# CM5.net
KiCad netlist of a schematic drawn in Altium Designer
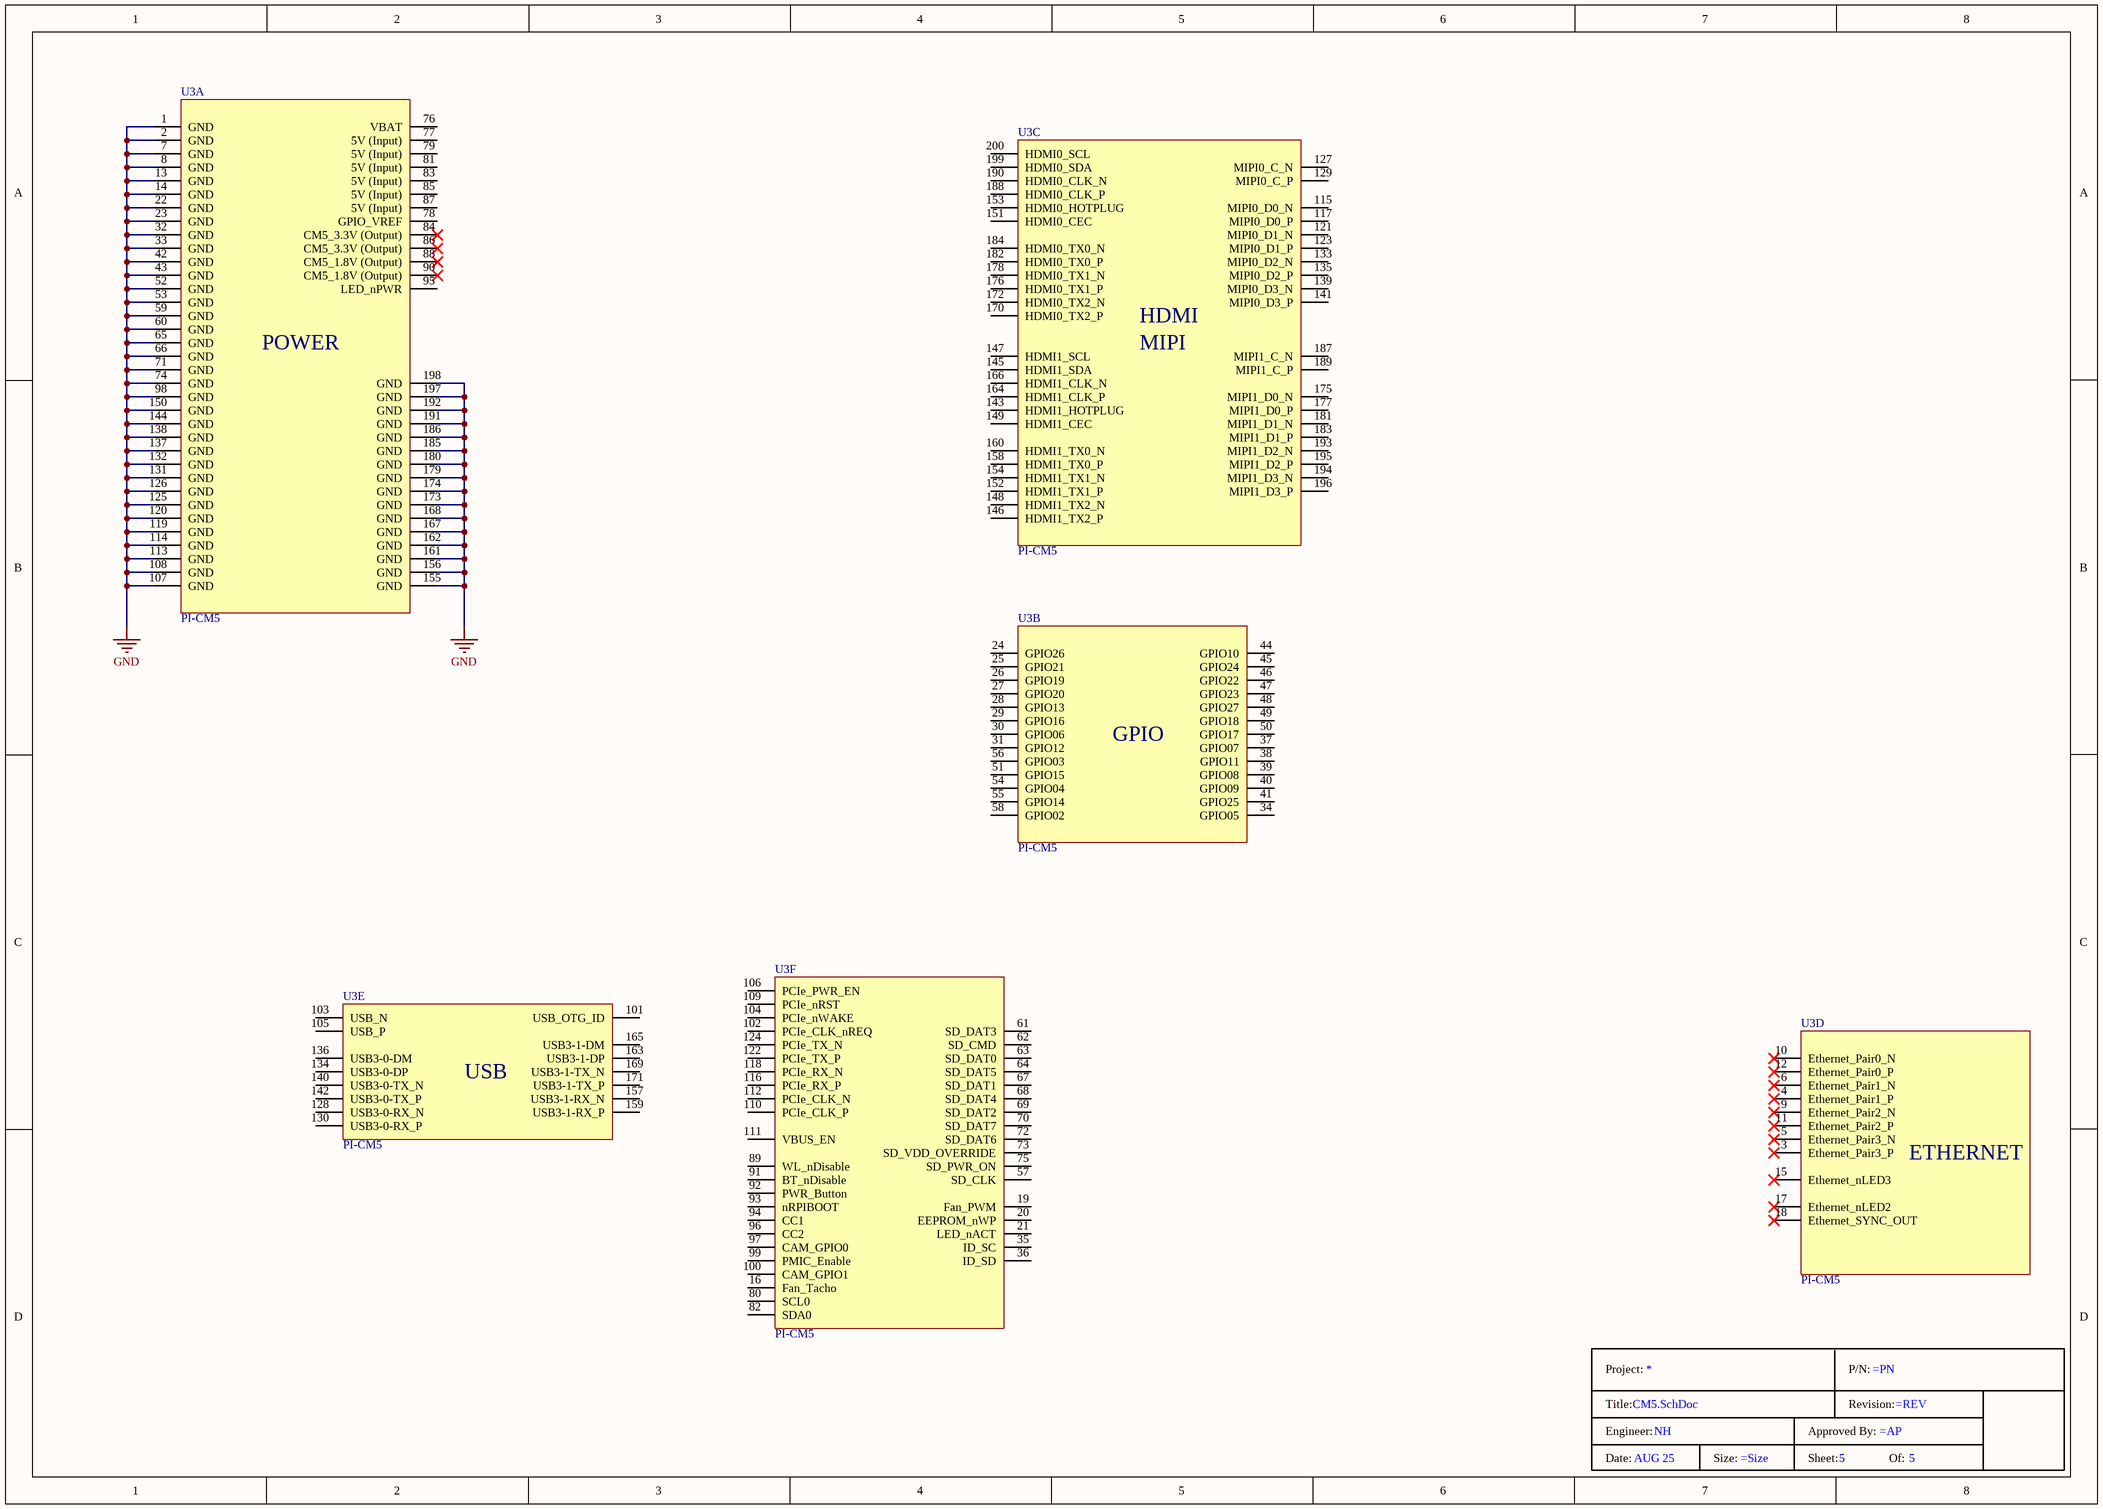
[diagram p0: CM5.SchDoc]

(export (version "E")
  (design (tool "Eeschema 10.0.6"))
  (components
    (comp (ref "*") (value "Tital_block_1") (libsource (lib "Graphical") (part "Tital_block_1")))
    (comp (ref "U3") (value "PI-CM5") (footprint "SC1562(PI-CM5)") (libsource (lib "IC") (part "PI-CM5")))
  )
  (nets
    (net (code "1") (name "GND") (class "Default")
      (node (ref "U3") (pin "1") (pinfunction "GND_1") (pintype "passive"))
      (node (ref "U3") (pin "107") (pinfunction "GND_107") (pintype "passive"))
      (node (ref "U3") (pin "108") (pinfunction "GND_108") (pintype "passive"))
      (node (ref "U3") (pin "113") (pinfunction "GND_113") (pintype "passive"))
      (node (ref "U3") (pin "114") (pinfunction "GND_114") (pintype "passive"))
      (node (ref "U3") (pin "119") (pinfunction "GND_119") (pintype "passive"))
      (node (ref "U3") (pin "120") (pinfunction "GND_120") (pintype "passive"))
      (node (ref "U3") (pin "125") (pinfunction "GND_125") (pintype "passive"))
      (node (ref "U3") (pin "126") (pinfunction "GND_126") (pintype "passive"))
      (node (ref "U3") (pin "13") (pinfunction "GND_13") (pintype "passive"))
      (node (ref "U3") (pin "131") (pinfunction "GND_131") (pintype "passive"))
      (node (ref "U3") (pin "132") (pinfunction "GND_132") (pintype "passive"))
      (node (ref "U3") (pin "137") (pinfunction "GND_137") (pintype "passive"))
      (node (ref "U3") (pin "138") (pinfunction "GND_138") (pintype "passive"))
      (node (ref "U3") (pin "14") (pinfunction "GND_14") (pintype "passive"))
      (node (ref "U3") (pin "144") (pinfunction "GND_144") (pintype "passive"))
      (node (ref "U3") (pin "150") (pinfunction "GND_150") (pintype "passive"))
      (node (ref "U3") (pin "155") (pinfunction "GND_155") (pintype "passive"))
      (node (ref "U3") (pin "156") (pinfunction "GND_156") (pintype "passive"))
      (node (ref "U3") (pin "161") (pinfunction "GND_161") (pintype "passive"))
      (node (ref "U3") (pin "162") (pinfunction "GND_162") (pintype "passive"))
      (node (ref "U3") (pin "167") (pinfunction "GND_167") (pintype "passive"))
      (node (ref "U3") (pin "168") (pinfunction "GND_168") (pintype "passive"))
      (node (ref "U3") (pin "173") (pinfunction "GND_173") (pintype "passive"))
      (node (ref "U3") (pin "174") (pinfunction "GND_174") (pintype "passive"))
      (node (ref "U3") (pin "179") (pinfunction "GND_179") (pintype "passive"))
      (node (ref "U3") (pin "180") (pinfunction "GND_180") (pintype "passive"))
      (node (ref "U3") (pin "185") (pinfunction "GND_185") (pintype "passive"))
      (node (ref "U3") (pin "186") (pinfunction "GND_186") (pintype "passive"))
      (node (ref "U3") (pin "191") (pinfunction "GND_191") (pintype "passive"))
      (node (ref "U3") (pin "192") (pinfunction "GND_192") (pintype "passive"))
      (node (ref "U3") (pin "197") (pinfunction "GND_197") (pintype "passive"))
      (node (ref "U3") (pin "198") (pinfunction "GND_198") (pintype "passive"))
      (node (ref "U3") (pin "2") (pinfunction "GND_2") (pintype "passive"))
      (node (ref "U3") (pin "22") (pinfunction "GND_22") (pintype "passive"))
      (node (ref "U3") (pin "23") (pinfunction "GND_23") (pintype "passive"))
      (node (ref "U3") (pin "32") (pinfunction "GND_32") (pintype "passive"))
      (node (ref "U3") (pin "33") (pinfunction "GND_33") (pintype "passive"))
      (node (ref "U3") (pin "42") (pinfunction "GND_42") (pintype "passive"))
      (node (ref "U3") (pin "43") (pinfunction "GND_43") (pintype "passive"))
      (node (ref "U3") (pin "52") (pinfunction "GND_52") (pintype "passive"))
      (node (ref "U3") (pin "53") (pinfunction "GND_53") (pintype "passive"))
      (node (ref "U3") (pin "59") (pinfunction "GND_59") (pintype "passive"))
      (node (ref "U3") (pin "60") (pinfunction "GND_60") (pintype "passive"))
      (node (ref "U3") (pin "65") (pinfunction "GND_65") (pintype "passive"))
      (node (ref "U3") (pin "66") (pinfunction "GND_66") (pintype "passive"))
      (node (ref "U3") (pin "7") (pinfunction "GND_7") (pintype "passive"))
      (node (ref "U3") (pin "71") (pinfunction "GND_71") (pintype "passive"))
      (node (ref "U3") (pin "74") (pinfunction "GND_74") (pintype "passive"))
      (node (ref "U3") (pin "8") (pinfunction "GND_8") (pintype "passive"))
      (node (ref "U3") (pin "98") (pinfunction "GND_98") (pintype "passive"))
    )
    (net (code "2") (name "unconnected-(U3A-5V_(Input)-Pad77)") (class "Default")
      (node (ref "U3") (pin "77") (pinfunction "5V_(Input)_77") (pintype "passive"))
    )
    (net (code "3") (name "unconnected-(U3A-5V_(Input)-Pad79)") (class "Default")
      (node (ref "U3") (pin "79") (pinfunction "5V_(Input)_79") (pintype "passive"))
    )
    (net (code "4") (name "unconnected-(U3A-5V_(Input)-Pad81)") (class "Default")
      (node (ref "U3") (pin "81") (pinfunction "5V_(Input)_81") (pintype "passive"))
    )
    (net (code "5") (name "unconnected-(U3A-5V_(Input)-Pad83)") (class "Default")
      (node (ref "U3") (pin "83") (pinfunction "5V_(Input)_83") (pintype "passive"))
    )
    (net (code "6") (name "unconnected-(U3A-5V_(Input)-Pad85)") (class "Default")
      (node (ref "U3") (pin "85") (pinfunction "5V_(Input)_85") (pintype "passive"))
    )
    (net (code "7") (name "unconnected-(U3A-5V_(Input)-Pad87)") (class "Default")
      (node (ref "U3") (pin "87") (pinfunction "5V_(Input)_87") (pintype "passive"))
    )
    (net (code "8") (name "unconnected-(U3A-CM5_1.8V_(Output)-Pad88)") (class "Default")
      (node (ref "U3") (pin "88") (pinfunction "CM5_1.8V_(Output)_88") (pintype "passive+no_connect"))
    )
    (net (code "9") (name "unconnected-(U3A-CM5_1.8V_(Output)-Pad90)") (class "Default")
      (node (ref "U3") (pin "90") (pinfunction "CM5_1.8V_(Output)_90") (pintype "passive+no_connect"))
    )
    (net (code "10") (name "unconnected-(U3A-CM5_3.3V_(Output)-Pad84)") (class "Default")
      (node (ref "U3") (pin "84") (pinfunction "CM5_3.3V_(Output)_84") (pintype "passive+no_connect"))
    )
    (net (code "11") (name "unconnected-(U3A-CM5_3.3V_(Output)-Pad86)") (class "Default")
      (node (ref "U3") (pin "86") (pinfunction "CM5_3.3V_(Output)_86") (pintype "passive+no_connect"))
    )
    (net (code "12") (name "unconnected-(U3A-GPIO_VREF-Pad78)") (class "Default")
      (node (ref "U3") (pin "78") (pinfunction "GPIO_VREF_78") (pintype "passive"))
    )
    (net (code "13") (name "unconnected-(U3A-LED_nPWR-Pad95)") (class "Default")
      (node (ref "U3") (pin "95") (pinfunction "LED_nPWR_95") (pintype "passive"))
    )
    (net (code "14") (name "unconnected-(U3A-VBAT-Pad76)") (class "Default")
      (node (ref "U3") (pin "76") (pinfunction "VBAT_76") (pintype "passive"))
    )
    (net (code "15") (name "unconnected-(U3B-GPIO02-Pad58)") (class "Default")
      (node (ref "U3") (pin "58") (pinfunction "GPIO02_58") (pintype "passive"))
    )
    (net (code "16") (name "unconnected-(U3B-GPIO03-Pad56)") (class "Default")
      (node (ref "U3") (pin "56") (pinfunction "GPIO03_56") (pintype "passive"))
    )
    (net (code "17") (name "unconnected-(U3B-GPIO04-Pad54)") (class "Default")
      (node (ref "U3") (pin "54") (pinfunction "GPIO04_54") (pintype "passive"))
    )
    (net (code "18") (name "unconnected-(U3B-GPIO05-Pad34)") (class "Default")
      (node (ref "U3") (pin "34") (pinfunction "GPIO05_34") (pintype "passive"))
    )
    (net (code "19") (name "unconnected-(U3B-GPIO06-Pad30)") (class "Default")
      (node (ref "U3") (pin "30") (pinfunction "GPIO06_30") (pintype "passive"))
    )
    (net (code "20") (name "unconnected-(U3B-GPIO07-Pad37)") (class "Default")
      (node (ref "U3") (pin "37") (pinfunction "GPIO07_37") (pintype "passive"))
    )
    (net (code "21") (name "unconnected-(U3B-GPIO08-Pad39)") (class "Default")
      (node (ref "U3") (pin "39") (pinfunction "GPIO08_39") (pintype "passive"))
    )
    (net (code "22") (name "unconnected-(U3B-GPIO09-Pad40)") (class "Default")
      (node (ref "U3") (pin "40") (pinfunction "GPIO09_40") (pintype "passive"))
    )
    (net (code "23") (name "unconnected-(U3B-GPIO10-Pad44)") (class "Default")
      (node (ref "U3") (pin "44") (pinfunction "GPIO10_44") (pintype "passive"))
    )
    (net (code "24") (name "unconnected-(U3B-GPIO11-Pad38)") (class "Default")
      (node (ref "U3") (pin "38") (pinfunction "GPIO11_38") (pintype "passive"))
    )
    (net (code "25") (name "unconnected-(U3B-GPIO12-Pad31)") (class "Default")
      (node (ref "U3") (pin "31") (pinfunction "GPIO12_31") (pintype "passive"))
    )
    (net (code "26") (name "unconnected-(U3B-GPIO13-Pad28)") (class "Default")
      (node (ref "U3") (pin "28") (pinfunction "GPIO13_28") (pintype "passive"))
    )
    (net (code "27") (name "unconnected-(U3B-GPIO14-Pad55)") (class "Default")
      (node (ref "U3") (pin "55") (pinfunction "GPIO14_55") (pintype "passive"))
    )
    (net (code "28") (name "unconnected-(U3B-GPIO15-Pad51)") (class "Default")
      (node (ref "U3") (pin "51") (pinfunction "GPIO15_51") (pintype "passive"))
    )
    (net (code "29") (name "unconnected-(U3B-GPIO16-Pad29)") (class "Default")
      (node (ref "U3") (pin "29") (pinfunction "GPIO16_29") (pintype "passive"))
    )
    (net (code "30") (name "unconnected-(U3B-GPIO17-Pad50)") (class "Default")
      (node (ref "U3") (pin "50") (pinfunction "GPIO17_50") (pintype "passive"))
    )
    (net (code "31") (name "unconnected-(U3B-GPIO18-Pad49)") (class "Default")
      (node (ref "U3") (pin "49") (pinfunction "GPIO18_49") (pintype "passive"))
    )
    (net (code "32") (name "unconnected-(U3B-GPIO19-Pad26)") (class "Default")
      (node (ref "U3") (pin "26") (pinfunction "GPIO19_26") (pintype "passive"))
    )
    (net (code "33") (name "unconnected-(U3B-GPIO20-Pad27)") (class "Default")
      (node (ref "U3") (pin "27") (pinfunction "GPIO20_27") (pintype "passive"))
    )
    (net (code "34") (name "unconnected-(U3B-GPIO21-Pad25)") (class "Default")
      (node (ref "U3") (pin "25") (pinfunction "GPIO21_25") (pintype "passive"))
    )
    (net (code "35") (name "unconnected-(U3B-GPIO22-Pad46)") (class "Default")
      (node (ref "U3") (pin "46") (pinfunction "GPIO22_46") (pintype "passive"))
    )
    (net (code "36") (name "unconnected-(U3B-GPIO23-Pad47)") (class "Default")
      (node (ref "U3") (pin "47") (pinfunction "GPIO23_47") (pintype "passive"))
    )
    (net (code "37") (name "unconnected-(U3B-GPIO24-Pad45)") (class "Default")
      (node (ref "U3") (pin "45") (pinfunction "GPIO24_45") (pintype "passive"))
    )
    (net (code "38") (name "unconnected-(U3B-GPIO25-Pad41)") (class "Default")
      (node (ref "U3") (pin "41") (pinfunction "GPIO25_41") (pintype "passive"))
    )
    (net (code "39") (name "unconnected-(U3B-GPIO26-Pad24)") (class "Default")
      (node (ref "U3") (pin "24") (pinfunction "GPIO26_24") (pintype "passive"))
    )
    (net (code "40") (name "unconnected-(U3B-GPIO27-Pad48)") (class "Default")
      (node (ref "U3") (pin "48") (pinfunction "GPIO27_48") (pintype "passive"))
    )
    (net (code "41") (name "unconnected-(U3C-HDMI0_CEC-Pad151)") (class "Default")
      (node (ref "U3") (pin "151") (pinfunction "HDMI0_CEC_151") (pintype "passive"))
    )
    (net (code "42") (name "unconnected-(U3C-HDMI0_CLK_N-Pad190)") (class "Default")
      (node (ref "U3") (pin "190") (pinfunction "HDMI0_CLK_N_190") (pintype "passive"))
    )
    (net (code "43") (name "unconnected-(U3C-HDMI0_CLK_P-Pad188)") (class "Default")
      (node (ref "U3") (pin "188") (pinfunction "HDMI0_CLK_P_188") (pintype "passive"))
    )
    (net (code "44") (name "unconnected-(U3C-HDMI0_HOTPLUG-Pad153)") (class "Default")
      (node (ref "U3") (pin "153") (pinfunction "HDMI0_HOTPLUG_153") (pintype "passive"))
    )
    (net (code "45") (name "unconnected-(U3C-HDMI0_SCL-Pad200)") (class "Default")
      (node (ref "U3") (pin "200") (pinfunction "HDMI0_SCL_200") (pintype "passive"))
    )
    (net (code "46") (name "unconnected-(U3C-HDMI0_SDA-Pad199)") (class "Default")
      (node (ref "U3") (pin "199") (pinfunction "HDMI0_SDA_199") (pintype "passive"))
    )
    (net (code "47") (name "unconnected-(U3C-HDMI0_TX0_N-Pad184)") (class "Default")
      (node (ref "U3") (pin "184") (pinfunction "HDMI0_TX0_N_184") (pintype "passive"))
    )
    (net (code "48") (name "unconnected-(U3C-HDMI0_TX0_P-Pad182)") (class "Default")
      (node (ref "U3") (pin "182") (pinfunction "HDMI0_TX0_P_182") (pintype "passive"))
    )
    (net (code "49") (name "unconnected-(U3C-HDMI0_TX1_N-Pad178)") (class "Default")
      (node (ref "U3") (pin "178") (pinfunction "HDMI0_TX1_N_178") (pintype "passive"))
    )
    (net (code "50") (name "unconnected-(U3C-HDMI0_TX1_P-Pad176)") (class "Default")
      (node (ref "U3") (pin "176") (pinfunction "HDMI0_TX1_P_176") (pintype "passive"))
    )
    (net (code "51") (name "unconnected-(U3C-HDMI0_TX2_N-Pad172)") (class "Default")
      (node (ref "U3") (pin "172") (pinfunction "HDMI0_TX2_N_172") (pintype "passive"))
    )
    (net (code "52") (name "unconnected-(U3C-HDMI0_TX2_P-Pad170)") (class "Default")
      (node (ref "U3") (pin "170") (pinfunction "HDMI0_TX2_P_170") (pintype "passive"))
    )
    (net (code "53") (name "unconnected-(U3C-HDMI1_CEC-Pad149)") (class "Default")
      (node (ref "U3") (pin "149") (pinfunction "HDMI1_CEC_149") (pintype "passive"))
    )
    (net (code "54") (name "unconnected-(U3C-HDMI1_CLK_N-Pad166)") (class "Default")
      (node (ref "U3") (pin "166") (pinfunction "HDMI1_CLK_N_166") (pintype "passive"))
    )
    (net (code "55") (name "unconnected-(U3C-HDMI1_CLK_P-Pad164)") (class "Default")
      (node (ref "U3") (pin "164") (pinfunction "HDMI1_CLK_P_164") (pintype "passive"))
    )
    (net (code "56") (name "unconnected-(U3C-HDMI1_HOTPLUG-Pad143)") (class "Default")
      (node (ref "U3") (pin "143") (pinfunction "HDMI1_HOTPLUG_143") (pintype "passive"))
    )
    (net (code "57") (name "unconnected-(U3C-HDMI1_SCL-Pad147)") (class "Default")
      (node (ref "U3") (pin "147") (pinfunction "HDMI1_SCL_147") (pintype "passive"))
    )
    (net (code "58") (name "unconnected-(U3C-HDMI1_SDA-Pad145)") (class "Default")
      (node (ref "U3") (pin "145") (pinfunction "HDMI1_SDA_145") (pintype "passive"))
    )
    (net (code "59") (name "unconnected-(U3C-HDMI1_TX0_N-Pad160)") (class "Default")
      (node (ref "U3") (pin "160") (pinfunction "HDMI1_TX0_N_160") (pintype "passive"))
    )
    (net (code "60") (name "unconnected-(U3C-HDMI1_TX0_P-Pad158)") (class "Default")
      (node (ref "U3") (pin "158") (pinfunction "HDMI1_TX0_P_158") (pintype "passive"))
    )
    (net (code "61") (name "unconnected-(U3C-HDMI1_TX1_N-Pad154)") (class "Default")
      (node (ref "U3") (pin "154") (pinfunction "HDMI1_TX1_N_154") (pintype "passive"))
    )
    (net (code "62") (name "unconnected-(U3C-HDMI1_TX1_P-Pad152)") (class "Default")
      (node (ref "U3") (pin "152") (pinfunction "HDMI1_TX1_P_152") (pintype "passive"))
    )
    (net (code "63") (name "unconnected-(U3C-HDMI1_TX2_N-Pad148)") (class "Default")
      (node (ref "U3") (pin "148") (pinfunction "HDMI1_TX2_N_148") (pintype "passive"))
    )
    (net (code "64") (name "unconnected-(U3C-HDMI1_TX2_P-Pad146)") (class "Default")
      (node (ref "U3") (pin "146") (pinfunction "HDMI1_TX2_P_146") (pintype "passive"))
    )
    (net (code "65") (name "unconnected-(U3C-MIPI0_C_N-Pad127)") (class "Default")
      (node (ref "U3") (pin "127") (pinfunction "MIPI0_C_N_127") (pintype "passive"))
    )
    (net (code "66") (name "unconnected-(U3C-MIPI0_C_P-Pad129)") (class "Default")
      (node (ref "U3") (pin "129") (pinfunction "MIPI0_C_P_129") (pintype "passive"))
    )
    (net (code "67") (name "unconnected-(U3C-MIPI0_D0_N-Pad115)") (class "Default")
      (node (ref "U3") (pin "115") (pinfunction "MIPI0_D0_N_115") (pintype "passive"))
    )
    (net (code "68") (name "unconnected-(U3C-MIPI0_D0_P-Pad117)") (class "Default")
      (node (ref "U3") (pin "117") (pinfunction "MIPI0_D0_P_117") (pintype "passive"))
    )
    (net (code "69") (name "unconnected-(U3C-MIPI0_D1_N-Pad121)") (class "Default")
      (node (ref "U3") (pin "121") (pinfunction "MIPI0_D1_N_121") (pintype "passive"))
    )
    (net (code "70") (name "unconnected-(U3C-MIPI0_D1_P-Pad123)") (class "Default")
      (node (ref "U3") (pin "123") (pinfunction "MIPI0_D1_P_123") (pintype "passive"))
    )
    (net (code "71") (name "unconnected-(U3C-MIPI0_D2_N-Pad133)") (class "Default")
      (node (ref "U3") (pin "133") (pinfunction "MIPI0_D2_N_133") (pintype "passive"))
    )
    (net (code "72") (name "unconnected-(U3C-MIPI0_D2_P-Pad135)") (class "Default")
      (node (ref "U3") (pin "135") (pinfunction "MIPI0_D2_P_135") (pintype "passive"))
    )
    (net (code "73") (name "unconnected-(U3C-MIPI0_D3_N-Pad139)") (class "Default")
      (node (ref "U3") (pin "139") (pinfunction "MIPI0_D3_N_139") (pintype "passive"))
    )
    (net (code "74") (name "unconnected-(U3C-MIPI0_D3_P-Pad141)") (class "Default")
      (node (ref "U3") (pin "141") (pinfunction "MIPI0_D3_P_141") (pintype "passive"))
    )
    (net (code "75") (name "unconnected-(U3C-MIPI1_C_N-Pad187)") (class "Default")
      (node (ref "U3") (pin "187") (pinfunction "MIPI1_C_N_187") (pintype "passive"))
    )
    (net (code "76") (name "unconnected-(U3C-MIPI1_C_P-Pad189)") (class "Default")
      (node (ref "U3") (pin "189") (pinfunction "MIPI1_C_P_189") (pintype "passive"))
    )
    (net (code "77") (name "unconnected-(U3C-MIPI1_D0_N-Pad175)") (class "Default")
      (node (ref "U3") (pin "175") (pinfunction "MIPI1_D0_N_175") (pintype "passive"))
    )
    (net (code "78") (name "unconnected-(U3C-MIPI1_D0_P-Pad177)") (class "Default")
      (node (ref "U3") (pin "177") (pinfunction "MIPI1_D0_P_177") (pintype "passive"))
    )
    (net (code "79") (name "unconnected-(U3C-MIPI1_D1_N-Pad181)") (class "Default")
      (node (ref "U3") (pin "181") (pinfunction "MIPI1_D1_N_181") (pintype "passive"))
    )
    (net (code "80") (name "unconnected-(U3C-MIPI1_D1_P-Pad183)") (class "Default")
      (node (ref "U3") (pin "183") (pinfunction "MIPI1_D1_P_183") (pintype "passive"))
    )
    (net (code "81") (name "unconnected-(U3C-MIPI1_D2_N-Pad193)") (class "Default")
      (node (ref "U3") (pin "193") (pinfunction "MIPI1_D2_N_193") (pintype "passive"))
    )
    (net (code "82") (name "unconnected-(U3C-MIPI1_D2_P-Pad195)") (class "Default")
      (node (ref "U3") (pin "195") (pinfunction "MIPI1_D2_P_195") (pintype "passive"))
    )
    (net (code "83") (name "unconnected-(U3C-MIPI1_D3_N-Pad194)") (class "Default")
      (node (ref "U3") (pin "194") (pinfunction "MIPI1_D3_N_194") (pintype "passive"))
    )
    (net (code "84") (name "unconnected-(U3C-MIPI1_D3_P-Pad196)") (class "Default")
      (node (ref "U3") (pin "196") (pinfunction "MIPI1_D3_P_196") (pintype "passive"))
    )
    (net (code "85") (name "unconnected-(U3D-Ethernet_Pair0_N-Pad10)") (class "Default")
      (node (ref "U3") (pin "10") (pinfunction "Ethernet_Pair0_N_10") (pintype "passive+no_connect"))
    )
    (net (code "86") (name "unconnected-(U3D-Ethernet_Pair0_P-Pad12)") (class "Default")
      (node (ref "U3") (pin "12") (pinfunction "Ethernet_Pair0_P_12") (pintype "passive+no_connect"))
    )
    (net (code "87") (name "unconnected-(U3D-Ethernet_Pair1_N-Pad6)") (class "Default")
      (node (ref "U3") (pin "6") (pinfunction "Ethernet_Pair1_N_6") (pintype "passive+no_connect"))
    )
    (net (code "88") (name "unconnected-(U3D-Ethernet_Pair1_P-Pad4)") (class "Default")
      (node (ref "U3") (pin "4") (pinfunction "Ethernet_Pair1_P_4") (pintype "passive+no_connect"))
    )
    (net (code "89") (name "unconnected-(U3D-Ethernet_Pair2_N-Pad9)") (class "Default")
      (node (ref "U3") (pin "9") (pinfunction "Ethernet_Pair2_N_9") (pintype "passive+no_connect"))
    )
    (net (code "90") (name "unconnected-(U3D-Ethernet_Pair2_P-Pad11)") (class "Default")
      (node (ref "U3") (pin "11") (pinfunction "Ethernet_Pair2_P_11") (pintype "passive+no_connect"))
    )
    (net (code "91") (name "unconnected-(U3D-Ethernet_Pair3_N-Pad5)") (class "Default")
      (node (ref "U3") (pin "5") (pinfunction "Ethernet_Pair3_N_5") (pintype "passive+no_connect"))
    )
    (net (code "92") (name "unconnected-(U3D-Ethernet_Pair3_P-Pad3)") (class "Default")
      (node (ref "U3") (pin "3") (pinfunction "Ethernet_Pair3_P_3") (pintype "passive+no_connect"))
    )
    (net (code "93") (name "unconnected-(U3D-Ethernet_SYNC_OUT-Pad18)") (class "Default")
      (node (ref "U3") (pin "18") (pinfunction "Ethernet_SYNC_OUT_18") (pintype "passive+no_connect"))
    )
    (net (code "94") (name "unconnected-(U3D-Ethernet_nLED2-Pad17)") (class "Default")
      (node (ref "U3") (pin "17") (pinfunction "Ethernet_nLED2_17") (pintype "passive+no_connect"))
    )
    (net (code "95") (name "unconnected-(U3D-Ethernet_nLED3-Pad15)") (class "Default")
      (node (ref "U3") (pin "15") (pinfunction "Ethernet_nLED3_15") (pintype "passive+no_connect"))
    )
    (net (code "96") (name "unconnected-(U3E-USB3-0-DM-Pad136)") (class "Default")
      (node (ref "U3") (pin "136") (pinfunction "USB3-0-DM_136") (pintype "passive"))
    )
    (net (code "97") (name "unconnected-(U3E-USB3-0-DP-Pad134)") (class "Default")
      (node (ref "U3") (pin "134") (pinfunction "USB3-0-DP_134") (pintype "passive"))
    )
    (net (code "98") (name "unconnected-(U3E-USB3-0-RX_N-Pad128)") (class "Default")
      (node (ref "U3") (pin "128") (pinfunction "USB3-0-RX_N_128") (pintype "passive"))
    )
    (net (code "99") (name "unconnected-(U3E-USB3-0-RX_P-Pad130)") (class "Default")
      (node (ref "U3") (pin "130") (pinfunction "USB3-0-RX_P_130") (pintype "passive"))
    )
    (net (code "100") (name "unconnected-(U3E-USB3-0-TX_N-Pad140)") (class "Default")
      (node (ref "U3") (pin "140") (pinfunction "USB3-0-TX_N_140") (pintype "passive"))
    )
    (net (code "101") (name "unconnected-(U3E-USB3-0-TX_P-Pad142)") (class "Default")
      (node (ref "U3") (pin "142") (pinfunction "USB3-0-TX_P_142") (pintype "passive"))
    )
    (net (code "102") (name "unconnected-(U3E-USB3-1-DM-Pad165)") (class "Default")
      (node (ref "U3") (pin "165") (pinfunction "USB3-1-DM_165") (pintype "passive"))
    )
    (net (code "103") (name "unconnected-(U3E-USB3-1-DP-Pad163)") (class "Default")
      (node (ref "U3") (pin "163") (pinfunction "USB3-1-DP_163") (pintype "passive"))
    )
    (net (code "104") (name "unconnected-(U3E-USB3-1-RX_N-Pad157)") (class "Default")
      (node (ref "U3") (pin "157") (pinfunction "USB3-1-RX_N_157") (pintype "passive"))
    )
    (net (code "105") (name "unconnected-(U3E-USB3-1-RX_P-Pad159)") (class "Default")
      (node (ref "U3") (pin "159") (pinfunction "USB3-1-RX_P_159") (pintype "passive"))
    )
    (net (code "106") (name "unconnected-(U3E-USB3-1-TX_N-Pad169)") (class "Default")
      (node (ref "U3") (pin "169") (pinfunction "USB3-1-TX_N_169") (pintype "passive"))
    )
    (net (code "107") (name "unconnected-(U3E-USB3-1-TX_P-Pad171)") (class "Default")
      (node (ref "U3") (pin "171") (pinfunction "USB3-1-TX_P_171") (pintype "passive"))
    )
    (net (code "108") (name "unconnected-(U3E-USB_N-Pad103)") (class "Default")
      (node (ref "U3") (pin "103") (pinfunction "USB_N_103") (pintype "passive"))
    )
    (net (code "109") (name "unconnected-(U3E-USB_OTG_ID-Pad101)") (class "Default")
      (node (ref "U3") (pin "101") (pinfunction "USB_OTG_ID_101") (pintype "passive"))
    )
    (net (code "110") (name "unconnected-(U3E-USB_P-Pad105)") (class "Default")
      (node (ref "U3") (pin "105") (pinfunction "USB_P_105") (pintype "passive"))
    )
    (net (code "111") (name "unconnected-(U3F-BT_nDisable-Pad91)") (class "Default")
      (node (ref "U3") (pin "91") (pinfunction "BT_nDisable_91") (pintype "passive"))
    )
    (net (code "112") (name "unconnected-(U3F-CAM_GPIO0-Pad97)") (class "Default")
      (node (ref "U3") (pin "97") (pinfunction "CAM_GPIO0_97") (pintype "passive"))
    )
    (net (code "113") (name "unconnected-(U3F-CAM_GPIO1-Pad100)") (class "Default")
      (node (ref "U3") (pin "100") (pinfunction "CAM_GPIO1_100") (pintype "passive"))
    )
    (net (code "114") (name "unconnected-(U3F-CC1-Pad94)") (class "Default")
      (node (ref "U3") (pin "94") (pinfunction "CC1_94") (pintype "passive"))
    )
    (net (code "115") (name "unconnected-(U3F-CC2-Pad96)") (class "Default")
      (node (ref "U3") (pin "96") (pinfunction "CC2_96") (pintype "passive"))
    )
    (net (code "116") (name "unconnected-(U3F-EEPROM_nWP-Pad20)") (class "Default")
      (node (ref "U3") (pin "20") (pinfunction "EEPROM_nWP_20") (pintype "passive"))
    )
    (net (code "117") (name "unconnected-(U3F-Fan_PWM-Pad19)") (class "Default")
      (node (ref "U3") (pin "19") (pinfunction "Fan_PWM_19") (pintype "passive"))
    )
    (net (code "118") (name "unconnected-(U3F-Fan_Tacho-Pad16)") (class "Default")
      (node (ref "U3") (pin "16") (pinfunction "Fan_Tacho_16") (pintype "passive"))
    )
    (net (code "119") (name "unconnected-(U3F-ID_SC-Pad35)") (class "Default")
      (node (ref "U3") (pin "35") (pinfunction "ID_SC_35") (pintype "passive"))
    )
    (net (code "120") (name "unconnected-(U3F-ID_SD-Pad36)") (class "Default")
      (node (ref "U3") (pin "36") (pinfunction "ID_SD_36") (pintype "passive"))
    )
    (net (code "121") (name "unconnected-(U3F-LED_nACT-Pad21)") (class "Default")
      (node (ref "U3") (pin "21") (pinfunction "LED_nACT_21") (pintype "passive"))
    )
    (net (code "122") (name "unconnected-(U3F-PCIe_CLK_N-Pad112)") (class "Default")
      (node (ref "U3") (pin "112") (pinfunction "PCIe_CLK_N_112") (pintype "passive"))
    )
    (net (code "123") (name "unconnected-(U3F-PCIe_CLK_P-Pad110)") (class "Default")
      (node (ref "U3") (pin "110") (pinfunction "PCIe_CLK_P_110") (pintype "passive"))
    )
    (net (code "124") (name "unconnected-(U3F-PCIe_CLK_nREQ-Pad102)") (class "Default")
      (node (ref "U3") (pin "102") (pinfunction "PCIe_CLK_nREQ_102") (pintype "passive"))
    )
    (net (code "125") (name "unconnected-(U3F-PCIe_PWR_EN-Pad106)") (class "Default")
      (node (ref "U3") (pin "106") (pinfunction "PCIe_PWR_EN_106") (pintype "passive"))
    )
    (net (code "126") (name "unconnected-(U3F-PCIe_RX_N-Pad118)") (class "Default")
      (node (ref "U3") (pin "118") (pinfunction "PCIe_RX_N_118") (pintype "passive"))
    )
    (net (code "127") (name "unconnected-(U3F-PCIe_RX_P-Pad116)") (class "Default")
      (node (ref "U3") (pin "116") (pinfunction "PCIe_RX_P_116") (pintype "passive"))
    )
    (net (code "128") (name "unconnected-(U3F-PCIe_TX_N-Pad124)") (class "Default")
      (node (ref "U3") (pin "124") (pinfunction "PCIe_TX_N_124") (pintype "passive"))
    )
    (net (code "129") (name "unconnected-(U3F-PCIe_TX_P-Pad122)") (class "Default")
      (node (ref "U3") (pin "122") (pinfunction "PCIe_TX_P_122") (pintype "passive"))
    )
    (net (code "130") (name "unconnected-(U3F-PCIe_nRST-Pad109)") (class "Default")
      (node (ref "U3") (pin "109") (pinfunction "PCIe_nRST_109") (pintype "passive"))
    )
    (net (code "131") (name "unconnected-(U3F-PCIe_nWAKE-Pad104)") (class "Default")
      (node (ref "U3") (pin "104") (pinfunction "PCIe_nWAKE_104") (pintype "passive"))
    )
    (net (code "132") (name "unconnected-(U3F-PMIC_Enable-Pad99)") (class "Default")
      (node (ref "U3") (pin "99") (pinfunction "PMIC_Enable_99") (pintype "passive"))
    )
    (net (code "133") (name "unconnected-(U3F-PWR_Button-Pad92)") (class "Default")
      (node (ref "U3") (pin "92") (pinfunction "PWR_Button_92") (pintype "passive"))
    )
    (net (code "134") (name "unconnected-(U3F-SCL0-Pad80)") (class "Default")
      (node (ref "U3") (pin "80") (pinfunction "SCL0_80") (pintype "passive"))
    )
    (net (code "135") (name "unconnected-(U3F-SDA0-Pad82)") (class "Default")
      (node (ref "U3") (pin "82") (pinfunction "SDA0_82") (pintype "passive"))
    )
    (net (code "136") (name "unconnected-(U3F-SD_CLK-Pad57)") (class "Default")
      (node (ref "U3") (pin "57") (pinfunction "SD_CLK_57") (pintype "passive"))
    )
    (net (code "137") (name "unconnected-(U3F-SD_CMD-Pad62)") (class "Default")
      (node (ref "U3") (pin "62") (pinfunction "SD_CMD_62") (pintype "passive"))
    )
    (net (code "138") (name "unconnected-(U3F-SD_DAT0-Pad63)") (class "Default")
      (node (ref "U3") (pin "63") (pinfunction "SD_DAT0_63") (pintype "passive"))
    )
    (net (code "139") (name "unconnected-(U3F-SD_DAT1-Pad67)") (class "Default")
      (node (ref "U3") (pin "67") (pinfunction "SD_DAT1_67") (pintype "passive"))
    )
    (net (code "140") (name "unconnected-(U3F-SD_DAT2-Pad69)") (class "Default")
      (node (ref "U3") (pin "69") (pinfunction "SD_DAT2_69") (pintype "passive"))
    )
    (net (code "141") (name "unconnected-(U3F-SD_DAT3-Pad61)") (class "Default")
      (node (ref "U3") (pin "61") (pinfunction "SD_DAT3_61") (pintype "passive"))
    )
    (net (code "142") (name "unconnected-(U3F-SD_DAT4-Pad68)") (class "Default")
      (node (ref "U3") (pin "68") (pinfunction "SD_DAT4_68") (pintype "passive"))
    )
    (net (code "143") (name "unconnected-(U3F-SD_DAT5-Pad64)") (class "Default")
      (node (ref "U3") (pin "64") (pinfunction "SD_DAT5_64") (pintype "passive"))
    )
    (net (code "144") (name "unconnected-(U3F-SD_DAT6-Pad72)") (class "Default")
      (node (ref "U3") (pin "72") (pinfunction "SD_DAT6_72") (pintype "passive"))
    )
    (net (code "145") (name "unconnected-(U3F-SD_DAT7-Pad70)") (class "Default")
      (node (ref "U3") (pin "70") (pinfunction "SD_DAT7_70") (pintype "passive"))
    )
    (net (code "146") (name "unconnected-(U3F-SD_PWR_ON-Pad75)") (class "Default")
      (node (ref "U3") (pin "75") (pinfunction "SD_PWR_ON_75") (pintype "passive"))
    )
    (net (code "147") (name "unconnected-(U3F-SD_VDD_OVERRIDE-Pad73)") (class "Default")
      (node (ref "U3") (pin "73") (pinfunction "SD_VDD_OVERRIDE_73") (pintype "passive"))
    )
    (net (code "148") (name "unconnected-(U3F-VBUS_EN-Pad111)") (class "Default")
      (node (ref "U3") (pin "111") (pinfunction "VBUS_EN_111") (pintype "passive"))
    )
    (net (code "149") (name "unconnected-(U3F-WL_nDisable-Pad89)") (class "Default")
      (node (ref "U3") (pin "89") (pinfunction "WL_nDisable_89") (pintype "passive"))
    )
    (net (code "150") (name "unconnected-(U3F-nRPIBOOT-Pad93)") (class "Default")
      (node (ref "U3") (pin "93") (pinfunction "nRPIBOOT_93") (pintype "passive"))
    )
  )
)
